# Display-Port.net
KiCad netlist of a schematic drawn in Altium Designer
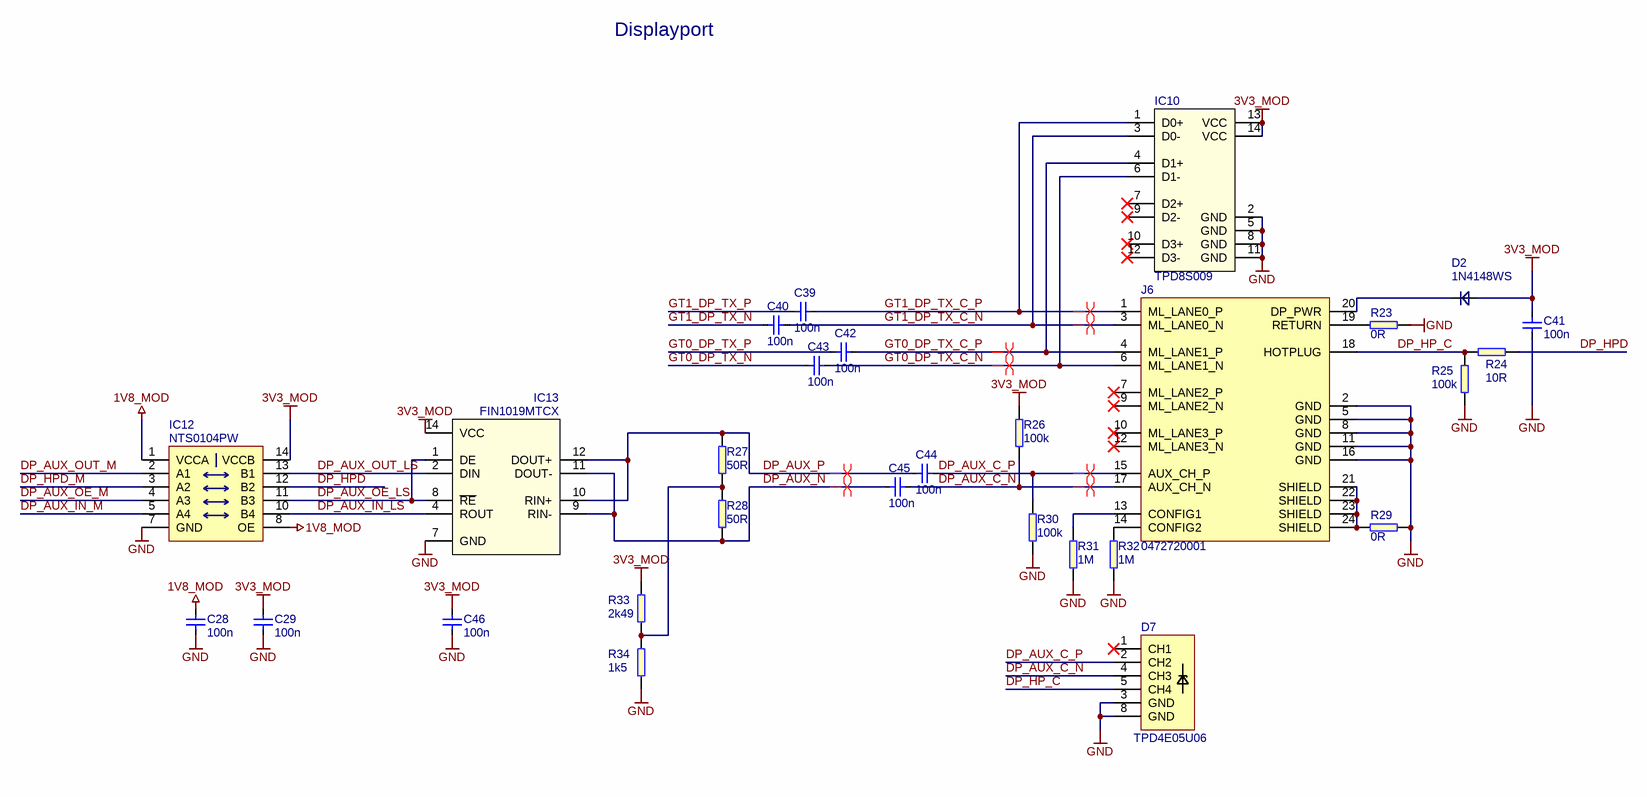
[diagram p0: Display-Port.SchDoc]

(export (version "E")
  (design (tool "Eeschema 10.0.6"))
  (components
    (comp (ref "C28")
      (value "100n")
      (footprint "0603")
      (description "MLCC SMT Capacitor 100nF 0603")
      (fields (field (name "PART NUMBER") "C_100n_0603") (field (name "MANUFACTURER") "WALSIN"))
      (libsource (lib "US-Plus-CPM") (part "C"))
    )
    (comp (ref "C29")
      (value "100n")
      (footprint "0603")
      (description "MLCC SMT Capacitor 100nF 0603")
      (fields (field (name "PART NUMBER") "C_100n_0603") (field (name "MANUFACTURER") "WALSIN"))
      (libsource (lib "US-Plus-CPM") (part "C"))
    )
    (comp (ref "C39")
      (value "100n")
      (footprint "0603")
      (description "MLCC SMT Capacitor 100nF 0603")
      (fields (field (name "PART NUMBER") "C_100n_0603") (field (name "MANUFACTURER") "WALSIN"))
      (libsource (lib "US-Plus-CPM") (part "C"))
    )
    (comp (ref "C40")
      (value "100n")
      (footprint "0603")
      (description "MLCC SMT Capacitor 100nF 0603")
      (fields (field (name "PART NUMBER") "C_100n_0603") (field (name "MANUFACTURER") "WALSIN"))
      (libsource (lib "US-Plus-CPM") (part "C"))
    )
    (comp (ref "C41")
      (value "100n")
      (footprint "0603")
      (description "MLCC SMT Capacitor 100nF 0603")
      (fields (field (name "PART NUMBER") "C_100n_0603") (field (name "MANUFACTURER") "WALSIN"))
      (libsource (lib "US-Plus-CPM") (part "C"))
    )
    (comp (ref "C42")
      (value "100n")
      (footprint "0603")
      (description "MLCC SMT Capacitor 100nF 0603")
      (fields (field (name "PART NUMBER") "C_100n_0603") (field (name "MANUFACTURER") "WALSIN"))
      (libsource (lib "US-Plus-CPM") (part "C"))
    )
    (comp (ref "C43")
      (value "100n")
      (footprint "0603")
      (description "MLCC SMT Capacitor 100nF 0603")
      (fields (field (name "PART NUMBER") "C_100n_0603") (field (name "MANUFACTURER") "WALSIN"))
      (libsource (lib "US-Plus-CPM") (part "C"))
    )
    (comp (ref "C44")
      (value "100n")
      (footprint "0603")
      (description "MLCC SMT Capacitor 100nF 0603")
      (fields (field (name "PART NUMBER") "C_100n_0603") (field (name "MANUFACTURER") "WALSIN"))
      (libsource (lib "US-Plus-CPM") (part "C"))
    )
    (comp (ref "C45")
      (value "100n")
      (footprint "0603")
      (description "MLCC SMT Capacitor 100nF 0603")
      (fields (field (name "PART NUMBER") "C_100n_0603") (field (name "MANUFACTURER") "WALSIN"))
      (libsource (lib "US-Plus-CPM") (part "C"))
    )
    (comp (ref "C46")
      (value "100n")
      (footprint "0603")
      (description "MLCC SMT Capacitor 100nF 0603")
      (fields (field (name "PART NUMBER") "C_100n_0603") (field (name "MANUFACTURER") "WALSIN"))
      (libsource (lib "US-Plus-CPM") (part "C"))
    )
    (comp (ref "D2")
      (value "1N4148WS")
      (footprint "SOD-323")
      (description "Diode small signal")
      (fields (field (name "MANUFACTURER") "MULTICOMP"))
      (libsource (lib "US-Plus-CPM") (part "diode"))
    )
    (comp (ref "D7")
      (value "TPD4E05U06")
      (footprint "TPD4E05U06_PASS")
      (description "ESD Suppressors 4-CH")
      (fields
        (field (name "PART NUMBER") "TPD4E05U06_PASS")
        (field (name "MANUFACTURER") "Texas Instruments")
      )
      (libsource (lib "US-Plus-CPM") (part "TPD4E05U06"))
    )
    (comp (ref "IC10")
      (value "TPD8S009")
      (footprint "SON-15")
      (description "8-Channel ESD Protection for DisplayPort and HDMI")
      (fields
        (field (name "PART NUMBER") "TPD8S009")
        (field (name "MANUFACTURER") "TEXAS INSTRUMENTS")
        (field (name "MPN") "TPD8S009DSMR")
      )
      (libsource (lib "US-Plus-CPM") (part "TPD8S009"))
    )
    (comp (ref "IC12")
      (value "NTS0104PW")
      (footprint "TSSOP-14")
      (description "4 bit voltage level translator")
      (fields (field (name "MANUFACTURER") "NXP"))
      (libsource (lib "US-Plus-CPM") (part "NTS0104"))
    )
    (comp (ref "IC13")
      (value "FIN1019MTCX")
      (footprint "TSSOP-14")
      (description "3.3 V LVDS High Speed Differential Driver Receiver")
      (fields (field (name "MANUFACTURER") "OM SEMICONDUCTOR"))
      (libsource (lib "US-Plus-CPM") (part "FIN1019"))
    )
    (comp (ref "J6")
      (value "0472720001")
      (fields (field (name "MANUFACTURER") "Molex"))
      (libsource (lib "US-Plus-CPM") (part "CON-Molex-047272-0001"))
    )
    (comp (ref "R23")
      (value "0R")
      (footprint "0603")
      (description "SMT Resistor 0R 0603")
      (fields (field (name "PART NUMBER") "R_0R_0603") (field (name "MANUFACTURER") "BOURNS"))
      (libsource (lib "") (part "R_1"))
    )
    (comp (ref "R24")
      (value "10R")
      (footprint "0603")
      (description "SMT Resistor 10R 0603")
      (fields (field (name "PART NUMBER") "R_10R_0603") (field (name "MANUFACTURER") "MULTICOMP"))
      (libsource (lib "") (part "R_1"))
    )
    (comp (ref "R25")
      (value "100k")
      (footprint "0603")
      (description "SMT Resistor 100k 0603")
      (fields (field (name "PART NUMBER") "R_100k_0603") (field (name "MANUFACTURER") "BOURNS"))
      (libsource (lib "US-Plus-CPM") (part "R"))
    )
    (comp (ref "R26")
      (value "100k")
      (footprint "0603")
      (description "SMT Resistor 100k 0603 1%")
      (fields (field (name "PART NUMBER") "R_100k_0603_1%") (field (name "MANUFACTURER") "BOURNS"))
      (libsource (lib "US-Plus-CPM") (part "R"))
    )
    (comp (ref "R27")
      (value "50R")
      (footprint "0603")
      (description "SMT Resistor 50R 0603 1%")
      (fields (field (name "PART NUMBER") "R_50R_0603_1%") (field (name "MANUFACTURER") "VISHAY"))
      (libsource (lib "US-Plus-CPM") (part "R"))
    )
    (comp (ref "R28")
      (value "50R")
      (footprint "0603")
      (description "SMT Resistor 50R 0603 1%")
      (fields (field (name "PART NUMBER") "R_50R_0603_1%") (field (name "MANUFACTURER") "VISHAY"))
      (libsource (lib "US-Plus-CPM") (part "R"))
    )
    (comp (ref "R29")
      (value "0R")
      (footprint "0603")
      (description "SMT Resistor 0R 0603")
      (fields (field (name "PART NUMBER") "R_0R_0603") (field (name "MANUFACTURER") "BOURNS"))
      (libsource (lib "") (part "R_1"))
    )
    (comp (ref "R30")
      (value "100k")
      (footprint "0603")
      (description "SMT Resistor 100k 0603 1%")
      (fields (field (name "PART NUMBER") "R_100k_0603_1%") (field (name "MANUFACTURER") "BOURNS"))
      (libsource (lib "US-Plus-CPM") (part "R"))
    )
    (comp (ref "R31")
      (value "1M")
      (footprint "0603")
      (description "SMT Resistor 1M 0603")
      (fields (field (name "PART NUMBER") "R_1M_0603") (field (name "MANUFACTURER") "BOURNS"))
      (libsource (lib "US-Plus-CPM") (part "R"))
    )
    (comp (ref "R32")
      (value "1M")
      (footprint "0603")
      (description "SMT Resistor 1M 0603")
      (fields (field (name "PART NUMBER") "R_1M_0603") (field (name "MANUFACTURER") "BOURNS"))
      (libsource (lib "US-Plus-CPM") (part "R"))
    )
    (comp (ref "R33")
      (value "2k49")
      (footprint "0603")
      (description "SMT Resistor 2k49 0603 1%")
      (fields (field (name "PART NUMBER") "R_2k49_0603_1%") (field (name "MANUFACTURER") "Vishay"))
      (libsource (lib "US-Plus-CPM") (part "R"))
    )
    (comp (ref "R34")
      (value "1k5")
      (footprint "0603")
      (description "SMT Resistor 1k5 0603")
      (fields
        (field (name "PART NUMBER") "R_1k5_0603")
        (field (name "MANUFACTURER") "TE CONNECTIVITY / NEOHM")
      )
      (libsource (lib "US-Plus-CPM") (part "R"))
    )
  )
  (nets
    (net (code "1") (name "/DP_AUX_C_N") (class "Default")
      (node (ref "C45") (pin "2") (pinfunction "2_2") (pintype "passive"))
      (node (ref "D7") (pin "4") (pinfunction "CH3_4") (pintype "passive"))
      (node (ref "J6") (pin "17") (pinfunction "AUX_CH_N_17") (pintype "passive"))
      (node (ref "R26") (pin "1") (pintype "passive"))
    )
    (net (code "2") (name "/DP_AUX_C_P") (class "Default")
      (node (ref "C44") (pin "2") (pinfunction "2_2") (pintype "passive"))
      (node (ref "D7") (pin "2") (pinfunction "CH2_2") (pintype "passive"))
      (node (ref "J6") (pin "15") (pinfunction "AUX_CH_P_15") (pintype "passive"))
      (node (ref "R30") (pin "2") (pintype "passive"))
    )
    (net (code "3") (name "/DP_AUX_IN_LS") (class "Default")
      (node (ref "IC12") (pin "10") (pinfunction "B4_10") (pintype "passive"))
      (node (ref "IC13") (pin "4") (pinfunction "ROUT_4") (pintype "passive"))
    )
    (net (code "4") (name "/DP_AUX_IN_M") (class "Default")
      (node (ref "IC12") (pin "5") (pinfunction "A4_5") (pintype "passive"))
    )
    (net (code "5") (name "/DP_AUX_N") (class "Default")
      (node (ref "C45") (pin "1") (pinfunction "1_1") (pintype "passive"))
      (node (ref "IC13") (pin "11") (pinfunction "DOUT-_11") (pintype "passive"))
      (node (ref "IC13") (pin "9") (pinfunction "RIN-_9") (pintype "passive"))
      (node (ref "R28") (pin "1") (pintype "passive"))
    )
    (net (code "6") (name "/DP_AUX_OE_LS") (class "Default")
      (node (ref "IC12") (pin "11") (pinfunction "B3_11") (pintype "passive"))
      (node (ref "IC13") (pin "1") (pinfunction "DE_1") (pintype "passive"))
      (node (ref "IC13") (pin "8") (pinfunction "~{RE}_8") (pintype "passive"))
    )
    (net (code "7") (name "/DP_AUX_OE_M") (class "Default")
      (node (ref "IC12") (pin "4") (pinfunction "A3_4") (pintype "passive"))
    )
    (net (code "8") (name "/DP_AUX_OUT_LS") (class "Default")
      (node (ref "IC12") (pin "13") (pinfunction "B1_13") (pintype "passive"))
      (node (ref "IC13") (pin "2") (pinfunction "DIN_2") (pintype "passive"))
    )
    (net (code "9") (name "/DP_AUX_OUT_M") (class "Default")
      (node (ref "IC12") (pin "2") (pinfunction "A1_2") (pintype "passive"))
    )
    (net (code "10") (name "/DP_AUX_P") (class "Default")
      (node (ref "C44") (pin "1") (pinfunction "1_1") (pintype "passive"))
      (node (ref "IC13") (pin "10") (pinfunction "RIN+_10") (pintype "passive"))
      (node (ref "IC13") (pin "12") (pinfunction "DOUT+_12") (pintype "passive"))
      (node (ref "R27") (pin "2") (pintype "passive"))
    )
    (net (code "11") (name "/DP_HPD") (class "Default")
      (node (ref "IC12") (pin "12") (pinfunction "B2_12") (pintype "passive"))
      (node (ref "R24") (pin "2") (pintype "passive"))
    )
    (net (code "12") (name "/DP_HPD_M") (class "Default")
      (node (ref "IC12") (pin "3") (pinfunction "A2_3") (pintype "passive"))
    )
    (net (code "13") (name "/DP_HP_C") (class "Default")
      (node (ref "D7") (pin "5") (pinfunction "CH4_5") (pintype "passive"))
      (node (ref "J6") (pin "18") (pinfunction "HOTPLUG_18") (pintype "passive"))
      (node (ref "R24") (pin "1") (pintype "passive"))
      (node (ref "R25") (pin "2") (pintype "passive"))
    )
    (net (code "14") (name "/GT0_DP_TX_C_N") (class "Default")
      (node (ref "C43") (pin "2") (pinfunction "2_2") (pintype "passive"))
      (node (ref "IC10") (pin "6") (pinfunction "D1-_6") (pintype "passive"))
      (node (ref "J6") (pin "6") (pinfunction "ML_LANE1_N_6") (pintype "passive"))
    )
    (net (code "15") (name "/GT0_DP_TX_C_P") (class "Default")
      (node (ref "C42") (pin "2") (pinfunction "2_2") (pintype "passive"))
      (node (ref "IC10") (pin "4") (pinfunction "D1+_4") (pintype "passive"))
      (node (ref "J6") (pin "4") (pinfunction "ML_LANE1_P_4") (pintype "passive"))
    )
    (net (code "16") (name "/GT0_DP_TX_N") (class "Default")
      (node (ref "C43") (pin "1") (pinfunction "1_1") (pintype "passive"))
    )
    (net (code "17") (name "/GT0_DP_TX_P") (class "Default")
      (node (ref "C42") (pin "1") (pinfunction "1_1") (pintype "passive"))
    )
    (net (code "18") (name "/GT1_DP_TX_C_N") (class "Default")
      (node (ref "C40") (pin "2") (pinfunction "2_2") (pintype "passive"))
      (node (ref "IC10") (pin "3") (pinfunction "D0-_3") (pintype "passive"))
      (node (ref "J6") (pin "3") (pinfunction "ML_LANE0_N_3") (pintype "passive"))
    )
    (net (code "19") (name "/GT1_DP_TX_C_P") (class "Default")
      (node (ref "C39") (pin "2") (pinfunction "2_2") (pintype "passive"))
      (node (ref "IC10") (pin "1") (pinfunction "D0+_1") (pintype "passive"))
      (node (ref "J6") (pin "1") (pinfunction "ML_LANE0_P_1") (pintype "passive"))
    )
    (net (code "20") (name "/GT1_DP_TX_N") (class "Default")
      (node (ref "C40") (pin "1") (pinfunction "1_1") (pintype "passive"))
    )
    (net (code "21") (name "/GT1_DP_TX_P") (class "Default")
      (node (ref "C39") (pin "1") (pinfunction "1_1") (pintype "passive"))
    )
    (net (code "22") (name "1V8_MOD") (class "Default")
      (node (ref "C28") (pin "2") (pinfunction "2_2") (pintype "passive"))
      (node (ref "IC12") (pin "1") (pinfunction "VCCA_1") (pintype "passive"))
      (node (ref "IC12") (pin "8") (pinfunction "OE_8") (pintype "passive"))
    )
    (net (code "23") (name "3V3_MOD") (class "Default")
      (node (ref "C29") (pin "2") (pinfunction "2_2") (pintype "passive"))
      (node (ref "C41") (pin "1") (pinfunction "1_1") (pintype "passive"))
      (node (ref "C46") (pin "2") (pinfunction "2_2") (pintype "passive"))
      (node (ref "D2") (pin "A") (pinfunction "A_A") (pintype "passive"))
      (node (ref "IC10") (pin "13") (pinfunction "VCC_13") (pintype "passive"))
      (node (ref "IC10") (pin "14") (pinfunction "VCC_14") (pintype "passive"))
      (node (ref "IC12") (pin "14") (pinfunction "VCCB_14") (pintype "passive"))
      (node (ref "IC13") (pin "14") (pinfunction "VCC_14") (pintype "passive"))
      (node (ref "R26") (pin "2") (pintype "passive"))
      (node (ref "R33") (pin "2") (pintype "passive"))
    )
    (net (code "24") (name "GND") (class "Default")
      (node (ref "C28") (pin "1") (pinfunction "1_1") (pintype "passive"))
      (node (ref "C29") (pin "1") (pinfunction "1_1") (pintype "passive"))
      (node (ref "C41") (pin "2") (pinfunction "2_2") (pintype "passive"))
      (node (ref "C46") (pin "1") (pinfunction "1_1") (pintype "passive"))
      (node (ref "D7") (pin "3") (pinfunction "GND_3") (pintype "passive"))
      (node (ref "D7") (pin "8") (pinfunction "GND_8") (pintype "passive"))
      (node (ref "IC10") (pin "11") (pinfunction "GND_11") (pintype "passive"))
      (node (ref "IC10") (pin "2") (pinfunction "GND_2") (pintype "passive"))
      (node (ref "IC10") (pin "5") (pinfunction "GND_5") (pintype "passive"))
      (node (ref "IC10") (pin "8") (pinfunction "GND_8") (pintype "passive"))
      (node (ref "IC12") (pin "7") (pinfunction "GND_7") (pintype "passive"))
      (node (ref "IC13") (pin "7") (pinfunction "GND_7") (pintype "passive"))
      (node (ref "J6") (pin "11") (pinfunction "GND_11") (pintype "passive"))
      (node (ref "J6") (pin "16") (pinfunction "GND_16") (pintype "passive"))
      (node (ref "J6") (pin "2") (pinfunction "GND_2") (pintype "passive"))
      (node (ref "J6") (pin "5") (pinfunction "GND_5") (pintype "passive"))
      (node (ref "J6") (pin "8") (pinfunction "GND_8") (pintype "passive"))
      (node (ref "R23") (pin "2") (pintype "passive"))
      (node (ref "R25") (pin "1") (pintype "passive"))
      (node (ref "R29") (pin "2") (pintype "passive"))
      (node (ref "R30") (pin "1") (pintype "passive"))
      (node (ref "R31") (pin "1") (pintype "passive"))
      (node (ref "R32") (pin "1") (pintype "passive"))
      (node (ref "R34") (pin "1") (pintype "passive"))
    )
    (net (code "25") (name "Net-(J6-CONFIG1)") (class "Default")
      (node (ref "J6") (pin "13") (pinfunction "CONFIG1_13") (pintype "passive"))
      (node (ref "R31") (pin "2") (pintype "passive"))
    )
    (net (code "26") (name "Net-(J6-CONFIG2)") (class "Default")
      (node (ref "J6") (pin "14") (pinfunction "CONFIG2_14") (pintype "passive"))
      (node (ref "R32") (pin "2") (pintype "passive"))
    )
    (net (code "27") (name "Net-(J6-DP_PWR)") (class "Default")
      (node (ref "D2") (pin "C") (pinfunction "C_C") (pintype "passive"))
      (node (ref "J6") (pin "20") (pinfunction "DP_PWR_20") (pintype "passive"))
    )
    (net (code "28") (name "Net-(J6-RETURN)") (class "Default")
      (node (ref "J6") (pin "19") (pinfunction "RETURN_19") (pintype "passive"))
      (node (ref "R23") (pin "1") (pintype "passive"))
    )
    (net (code "29") (name "Net-(J6-SHIELD-Pad21)") (class "Default")
      (node (ref "J6") (pin "21") (pinfunction "SHIELD_21") (pintype "passive"))
      (node (ref "J6") (pin "22") (pinfunction "SHIELD_22") (pintype "passive"))
      (node (ref "J6") (pin "23") (pinfunction "SHIELD_23") (pintype "passive"))
      (node (ref "J6") (pin "24") (pinfunction "SHIELD_24") (pintype "passive"))
      (node (ref "R29") (pin "1") (pintype "passive"))
    )
    (net (code "30") (name "Net-(R27-Pad1)") (class "Default")
      (node (ref "R27") (pin "1") (pintype "passive"))
      (node (ref "R28") (pin "2") (pintype "passive"))
      (node (ref "R33") (pin "1") (pintype "passive"))
      (node (ref "R34") (pin "2") (pintype "passive"))
    )
    (net (code "31") (name "unconnected-(D7-CH1-Pad1)") (class "Default")
      (node (ref "D7") (pin "1") (pinfunction "CH1_1") (pintype "passive+no_connect"))
    )
    (net (code "32") (name "unconnected-(IC10-D2+-Pad7)") (class "Default")
      (node (ref "IC10") (pin "7") (pinfunction "D2+_7") (pintype "passive+no_connect"))
    )
    (net (code "33") (name "unconnected-(IC10-D2--Pad9)") (class "Default")
      (node (ref "IC10") (pin "9") (pinfunction "D2-_9") (pintype "passive+no_connect"))
    )
    (net (code "34") (name "unconnected-(IC10-D3+-Pad10)") (class "Default")
      (node (ref "IC10") (pin "10") (pinfunction "D3+_10") (pintype "passive+no_connect"))
    )
    (net (code "35") (name "unconnected-(IC10-D3--Pad12)") (class "Default")
      (node (ref "IC10") (pin "12") (pinfunction "D3-_12") (pintype "passive+no_connect"))
    )
    (net (code "36") (name "unconnected-(J6-ML_LANE2_N-Pad9)") (class "Default")
      (node (ref "J6") (pin "9") (pinfunction "ML_LANE2_N_9") (pintype "passive+no_connect"))
    )
    (net (code "37") (name "unconnected-(J6-ML_LANE2_P-Pad7)") (class "Default")
      (node (ref "J6") (pin "7") (pinfunction "ML_LANE2_P_7") (pintype "passive+no_connect"))
    )
    (net (code "38") (name "unconnected-(J6-ML_LANE3_N-Pad12)") (class "Default")
      (node (ref "J6") (pin "12") (pinfunction "ML_LANE3_N_12") (pintype "passive+no_connect"))
    )
    (net (code "39") (name "unconnected-(J6-ML_LANE3_P-Pad10)") (class "Default")
      (node (ref "J6") (pin "10") (pinfunction "ML_LANE3_P_10") (pintype "passive+no_connect"))
    )
  )
)
